# class_D_amplifier.net
KiCad netlist of a schematic drawn in Altium Designer
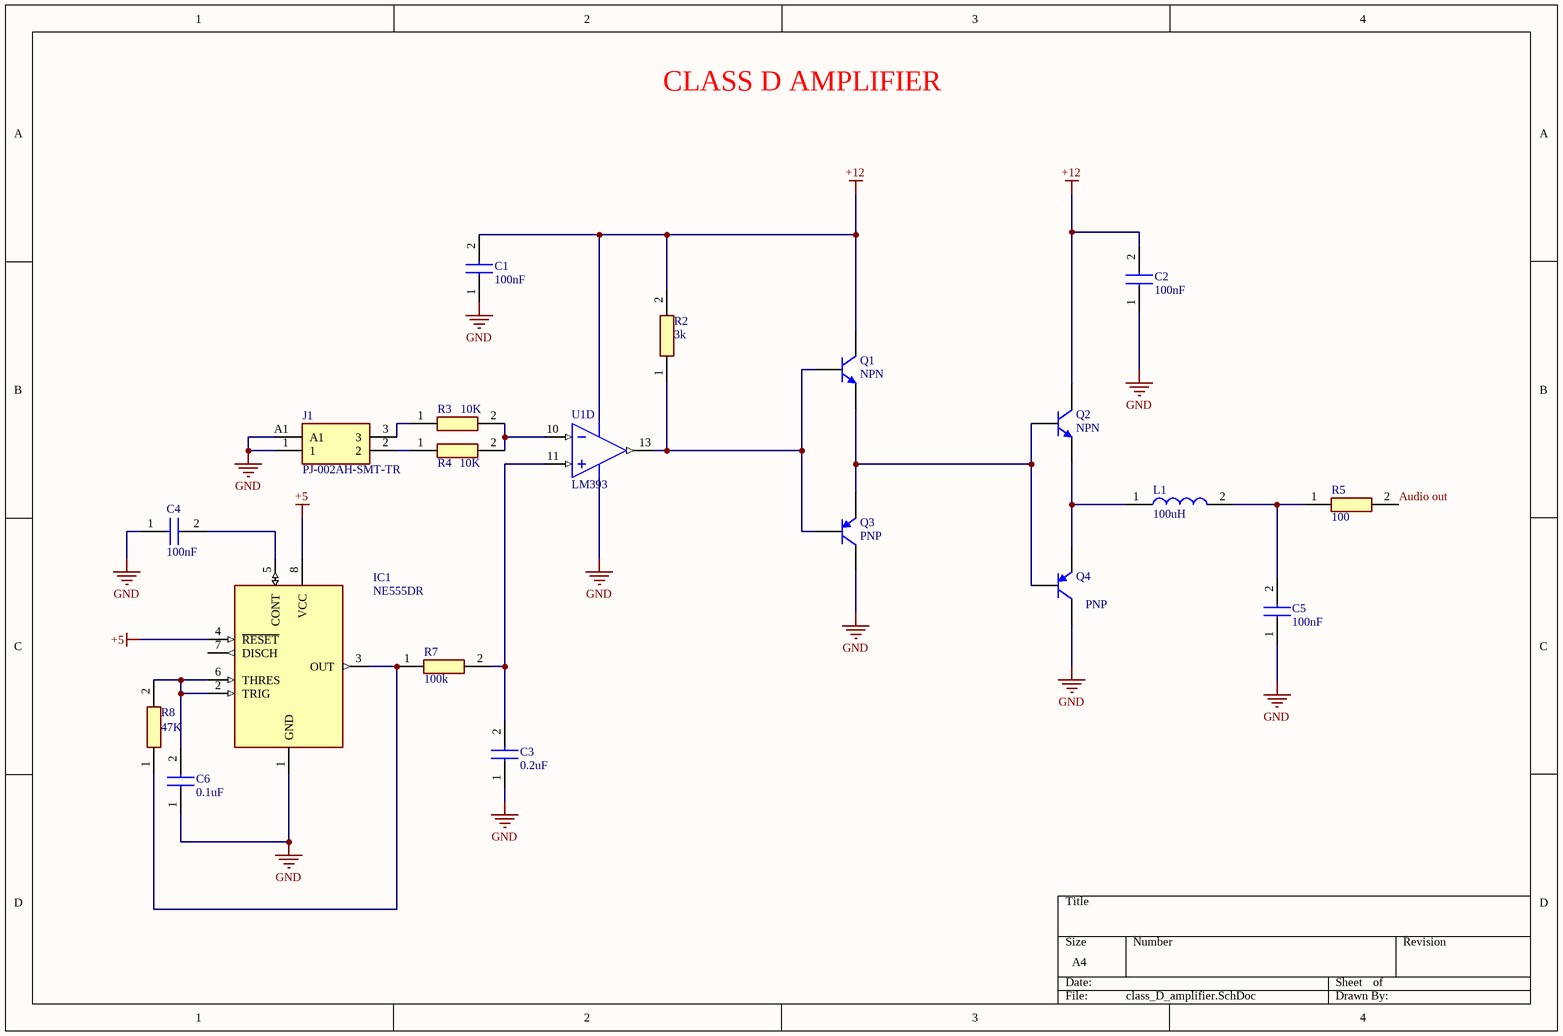
[diagram p0: class_D_amplifier.SchDoc]

(export (version "E")
  (design (tool "Eeschema 10.0.6"))
  (components
    (comp (ref "C1")
      (value "100nF")
      (footprint "SamacSys:CAPC1608X90N")
      (description "Capacitor")
      (fields
        (field (name "MANUFACTURER_PART_NUMBER") "GRM188R71C104MA01D")
        (field (name "MOUSER PART NUMBER") "81-GRM18R71C104MA01D")
      )
      (libsource (lib "SamacSys") (part "GRM188R71C104MA01D"))
    )
    (comp (ref "C2")
      (value "100nF")
      (footprint "SamacSys:CAPC1608X90N")
      (description "Capacitor")
      (fields
        (field (name "MANUFACTURER_PART_NUMBER") "GRM188R71C104MA01D")
        (field (name "MOUSER PART NUMBER") "81-GRM18R71C104MA01D")
      )
      (libsource (lib "SamacSys") (part "GRM188R71C104MA01D"))
    )
    (comp (ref "C3")
      (value "0.2uF")
      (footprint "SamacSys:CAPC1608X90N")
      (description "Capacitor")
      (fields
        (field (name "MANUFACTURER_PART_NUMBER") "GRM188R71C104MA01D")
        (field (name "MOUSER PART NUMBER") "81-GRM18R71C104MA01D")
      )
      (libsource (lib "SamacSys") (part "GRM188R71C104MA01D"))
    )
    (comp (ref "C4")
      (value "100nF")
      (footprint "SamacSys:CAPC1608X90N")
      (description "Capacitor")
      (fields
        (field (name "MANUFACTURER_PART_NUMBER") "GRM188R71C104MA01D")
        (field (name "MOUSER PART NUMBER") "81-GRM18R71C104MA01D")
      )
      (libsource (lib "SamacSys") (part "GRM188R71C104MA01D"))
    )
    (comp (ref "C5")
      (value "100nF")
      (footprint "SamacSys:CAPC1608X90N")
      (description "Capacitor")
      (fields
        (field (name "MANUFACTURER_PART_NUMBER") "GRM188R71C104MA01D")
        (field (name "MOUSER PART NUMBER") "81-GRM18R71C104MA01D")
      )
      (libsource (lib "SamacSys") (part "GRM188R71C104MA01D"))
    )
    (comp (ref "C6")
      (value "0.1uF")
      (footprint "SamacSys:CAPC1608X90N")
      (description "Capacitor")
      (fields
        (field (name "MANUFACTURER_PART_NUMBER") "GRM188R71C104MA01D")
        (field (name "MOUSER PART NUMBER") "81-GRM18R71C104MA01D")
      )
      (libsource (lib "SamacSys") (part "GRM188R71C104MA01D"))
    )
    (comp (ref "IC1")
      (value "NE555DR")
      (footprint "SOIC127P600X175-8N")
      (description "Integrated Circuit")
      (fields (field (name "MOUSER PART NUMBER") "595-NE555DR") (field (name "RS PART NUMBER") "1218414"))
      (libsource (lib "SamacSys") (part "NE555DR"))
    )
    (comp (ref "J1")
      (value "PJ-002AH-SMT-TR")
      (footprint "SamacSys:PJ002AHSMTTR")
      (description "Connector")
      (fields (field (name "MOUSER PART NUMBER") "490-PJ-002AH-SMT-TR"))
      (libsource (lib "SamacSys") (part "PJ-002AH-SMT-TR"))
    )
    (comp (ref "L1")
      (value "100uH")
      (footprint "SamacSys:IFDC3030EZER101M")
      (description "Inductor")
      (fields
        (field (name "MANUFACTURER_PART_NUMBER") "IFDC3030EZER101M")
        (field (name "MOUSER PART NUMBER") "70-IFDC3030EZER101M")
      )
      (libsource (lib "SamacSys") (part "IFDC3030EZER101M"))
    )
    (comp (ref "Q1")
      (value "NPN")
      (footprint "SOT-23B_L")
      (description "NPN Bipolar Transistor")
      (fields (field (name "PUBLISHER") "Altium Limited"))
      (libsource (lib "Miscellaneous Devices") (part "QNPN"))
    )
    (comp (ref "Q2")
      (value "NPN")
      (footprint "SOT-23B_L")
      (description "NPN Bipolar Transistor")
      (fields (field (name "PUBLISHER") "Altium Limited"))
      (libsource (lib "Miscellaneous Devices") (part "QNPN"))
    )
    (comp (ref "Q3")
      (value "PNP")
      (footprint "SOT-23B_L")
      (description "PNP Bipolar Transistor")
      (fields (field (name "PUBLISHER") "Altium Limited"))
      (libsource (lib "Miscellaneous Devices") (part "PNP"))
    )
    (comp (ref "Q4")
      (value "PNP")
      (footprint "SOT-23B_L")
      (description "PNP Bipolar Transistor")
      (fields (field (name "PUBLISHER") "Altium Limited"))
      (libsource (lib "Miscellaneous Devices") (part "PNP"))
    )
    (comp (ref "R2")
      (value "3k")
      (footprint "SamacSys:ERA3AEB101V")
      (description "Resistor")
      (fields
        (field (name "MANUFACTURER_PART_NUMBER") "ERA-3AED102V")
        (field (name "MOUSER PART NUMBER") "667-ERA-3AED102V")
      )
      (libsource (lib "SamacSys") (part "ERA-3AED102V"))
    )
    (comp (ref "R3")
      (value "10K")
      (footprint "SamacSys:ERA3AEB101V")
      (description "Resistor")
      (fields
        (field (name "MANUFACTURER_PART_NUMBER") "ERA-3AED102V")
        (field (name "MOUSER PART NUMBER") "667-ERA-3AED102V")
      )
      (libsource (lib "") (part "ERA-3AED102V_1"))
    )
    (comp (ref "R4")
      (value "10K")
      (footprint "SamacSys:ERA3AEB101V")
      (description "Resistor")
      (fields
        (field (name "MANUFACTURER_PART_NUMBER") "ERA-3AED102V")
        (field (name "MOUSER PART NUMBER") "667-ERA-3AED102V")
      )
      (libsource (lib "") (part "ERA-3AED102V_1"))
    )
    (comp (ref "R5")
      (value "100")
      (footprint "SamacSys:ERA3AEB101V")
      (description "Resistor")
      (fields
        (field (name "MANUFACTURER_PART_NUMBER") "ERA-3AED102V")
        (field (name "MOUSER PART NUMBER") "667-ERA-3AED102V")
      )
      (libsource (lib "") (part "ERA-3AED102V_1"))
    )
    (comp (ref "R7")
      (value "100k")
      (footprint "SamacSys:ERA3AEB101V")
      (description "Resistor")
      (fields
        (field (name "MANUFACTURER_PART_NUMBER") "ERA-3AED102V")
        (field (name "MOUSER PART NUMBER") "667-ERA-3AED102V")
      )
      (libsource (lib "") (part "ERA-3AED102V_1"))
    )
    (comp (ref "R8")
      (value "47K")
      (footprint "SamacSys:ERA3AEB101V")
      (description "Resistor")
      (fields
        (field (name "MANUFACTURER_PART_NUMBER") "ERA-3AED102V")
        (field (name "MOUSER PART NUMBER") "667-ERA-3AED102V")
      )
      (libsource (lib "SamacSys") (part "ERA-3AED102V"))
    )
    (comp (ref "U1")
      (value "LM393")
      (footprint "SOP65P640X120-8N")
      (description "Comparator General Purpose CMOS, DTL, ECL, MOS, Open-Collector, TTL 14-SOIC")
      (fields
        (field (name "MANUFACTURER") "TI National Semiconductor")
        (field (name "MANUFACTURER PART NUMBER") "LM339M/NOPB")
      )
      (libsource (lib "CONTROLYTICS") (part "IC_LM339M/NOPB"))
    )
  )
  (nets
    (net (code "1") (name "+5") (class "Default")
      (node (ref "IC1") (pin "4") (pinfunction "~{RESET}_4") (pintype "input"))
      (node (ref "IC1") (pin "8") (pinfunction "VCC_8") (pintype "power_in"))
    )
    (net (code "2") (name "+12") (class "Default")
      (node (ref "C1") (pin "2") (pinfunction "2_2") (pintype "passive"))
      (node (ref "C2") (pin "2") (pinfunction "2_2") (pintype "passive"))
      (node (ref "Q1") (pin "1") (pinfunction "C_1") (pintype "passive"))
      (node (ref "Q2") (pin "1") (pinfunction "C_1") (pintype "passive"))
      (node (ref "R2") (pin "2") (pinfunction "2_2") (pintype "passive"))
    )
    (net (code "3") (name "/Audio out") (class "Default")
      (node (ref "R5") (pin "2") (pinfunction "2_2") (pintype "passive"))
    )
    (net (code "4") (name "GND") (class "Default")
      (node (ref "C1") (pin "1") (pinfunction "1_1") (pintype "passive"))
      (node (ref "C2") (pin "1") (pinfunction "1_1") (pintype "passive"))
      (node (ref "C3") (pin "1") (pinfunction "1_1") (pintype "passive"))
      (node (ref "C4") (pin "1") (pinfunction "1_1") (pintype "passive"))
      (node (ref "C5") (pin "1") (pinfunction "1_1") (pintype "passive"))
      (node (ref "C6") (pin "1") (pinfunction "1_1") (pintype "passive"))
      (node (ref "IC1") (pin "1") (pinfunction "GND_1") (pintype "power_in"))
      (node (ref "J1") (pin "1") (pinfunction "1_1") (pintype "passive"))
      (node (ref "J1") (pin "A1") (pinfunction "A1_A1") (pintype "passive"))
      (node (ref "Q3") (pin "1") (pinfunction "C_1") (pintype "passive"))
      (node (ref "Q4") (pin "1") (pinfunction "C_1") (pintype "passive"))
    )
    (net (code "5") (name "Net-(C5-Pad2)") (class "Default")
      (node (ref "C5") (pin "2") (pinfunction "2_2") (pintype "passive"))
      (node (ref "L1") (pin "2") (pinfunction "2_2") (pintype "passive"))
      (node (ref "R5") (pin "1") (pinfunction "1_1") (pintype "passive"))
    )
    (net (code "6") (name "Net-(IC1-CONT)") (class "Default")
      (node (ref "C4") (pin "2") (pinfunction "2_2") (pintype "passive"))
      (node (ref "IC1") (pin "5") (pinfunction "CONT_5") (pintype "bidirectional"))
    )
    (net (code "7") (name "Net-(IC1-OUT)") (class "Default")
      (node (ref "IC1") (pin "3") (pinfunction "OUT_3") (pintype "output"))
      (node (ref "R7") (pin "1") (pinfunction "1_1") (pintype "passive"))
      (node (ref "R8") (pin "1") (pinfunction "1_1") (pintype "passive"))
    )
    (net (code "8") (name "Net-(IC1-THRES)") (class "Default")
      (node (ref "C6") (pin "2") (pinfunction "2_2") (pintype "passive"))
      (node (ref "IC1") (pin "2") (pinfunction "TRIG_2") (pintype "input"))
      (node (ref "IC1") (pin "6") (pinfunction "THRES_6") (pintype "input"))
      (node (ref "R8") (pin "2") (pinfunction "2_2") (pintype "passive"))
    )
    (net (code "9") (name "Net-(J1-Pad2)") (class "Default")
      (node (ref "J1") (pin "2") (pinfunction "2_2") (pintype "passive"))
      (node (ref "R4") (pin "1") (pinfunction "1_1") (pintype "passive"))
    )
    (net (code "10") (name "Net-(J1-Pad3)") (class "Default")
      (node (ref "J1") (pin "3") (pinfunction "3_3") (pintype "passive"))
      (node (ref "R3") (pin "1") (pinfunction "1_1") (pintype "passive"))
    )
    (net (code "11") (name "Net-(Q1-B)") (class "Default")
      (node (ref "Q1") (pin "2") (pinfunction "B_2") (pintype "passive"))
      (node (ref "Q3") (pin "2") (pinfunction "B_2") (pintype "passive"))
      (node (ref "R2") (pin "1") (pinfunction "1_1") (pintype "passive"))
      (node (ref "U1") (pin "13") (pinfunction "OUT4_13") (pintype "output"))
    )
    (net (code "12") (name "Net-(Q1-E)") (class "Default")
      (node (ref "Q1") (pin "3") (pinfunction "E_3") (pintype "passive"))
      (node (ref "Q2") (pin "2") (pinfunction "B_2") (pintype "passive"))
      (node (ref "Q3") (pin "3") (pinfunction "E_3") (pintype "passive"))
      (node (ref "Q4") (pin "2") (pinfunction "B_2") (pintype "passive"))
    )
    (net (code "13") (name "Net-(Q2-E)") (class "Default")
      (node (ref "L1") (pin "1") (pinfunction "1_1") (pintype "passive"))
      (node (ref "Q2") (pin "3") (pinfunction "E_3") (pintype "passive"))
      (node (ref "Q4") (pin "3") (pinfunction "E_3") (pintype "passive"))
    )
    (net (code "14") (name "Net-(U1D-IN4+)") (class "Default")
      (node (ref "C3") (pin "2") (pinfunction "2_2") (pintype "passive"))
      (node (ref "R7") (pin "2") (pinfunction "2_2") (pintype "passive"))
      (node (ref "U1") (pin "11") (pinfunction "IN4+_11") (pintype "input"))
    )
    (net (code "15") (name "Net-(U1D-IN4-)") (class "Default")
      (node (ref "R3") (pin "2") (pinfunction "2_2") (pintype "passive"))
      (node (ref "R4") (pin "2") (pinfunction "2_2") (pintype "passive"))
      (node (ref "U1") (pin "10") (pinfunction "IN4-_10") (pintype "input"))
    )
    (net (code "16") (name "unconnected-(IC1-DISCH-Pad7)") (class "Default")
      (node (ref "IC1") (pin "7") (pinfunction "DISCH_7") (pintype "output"))
    )
  )
)
